# lab2_lyahovskij_buck.net
KiCad netlist of a schematic drawn in Altium Designer
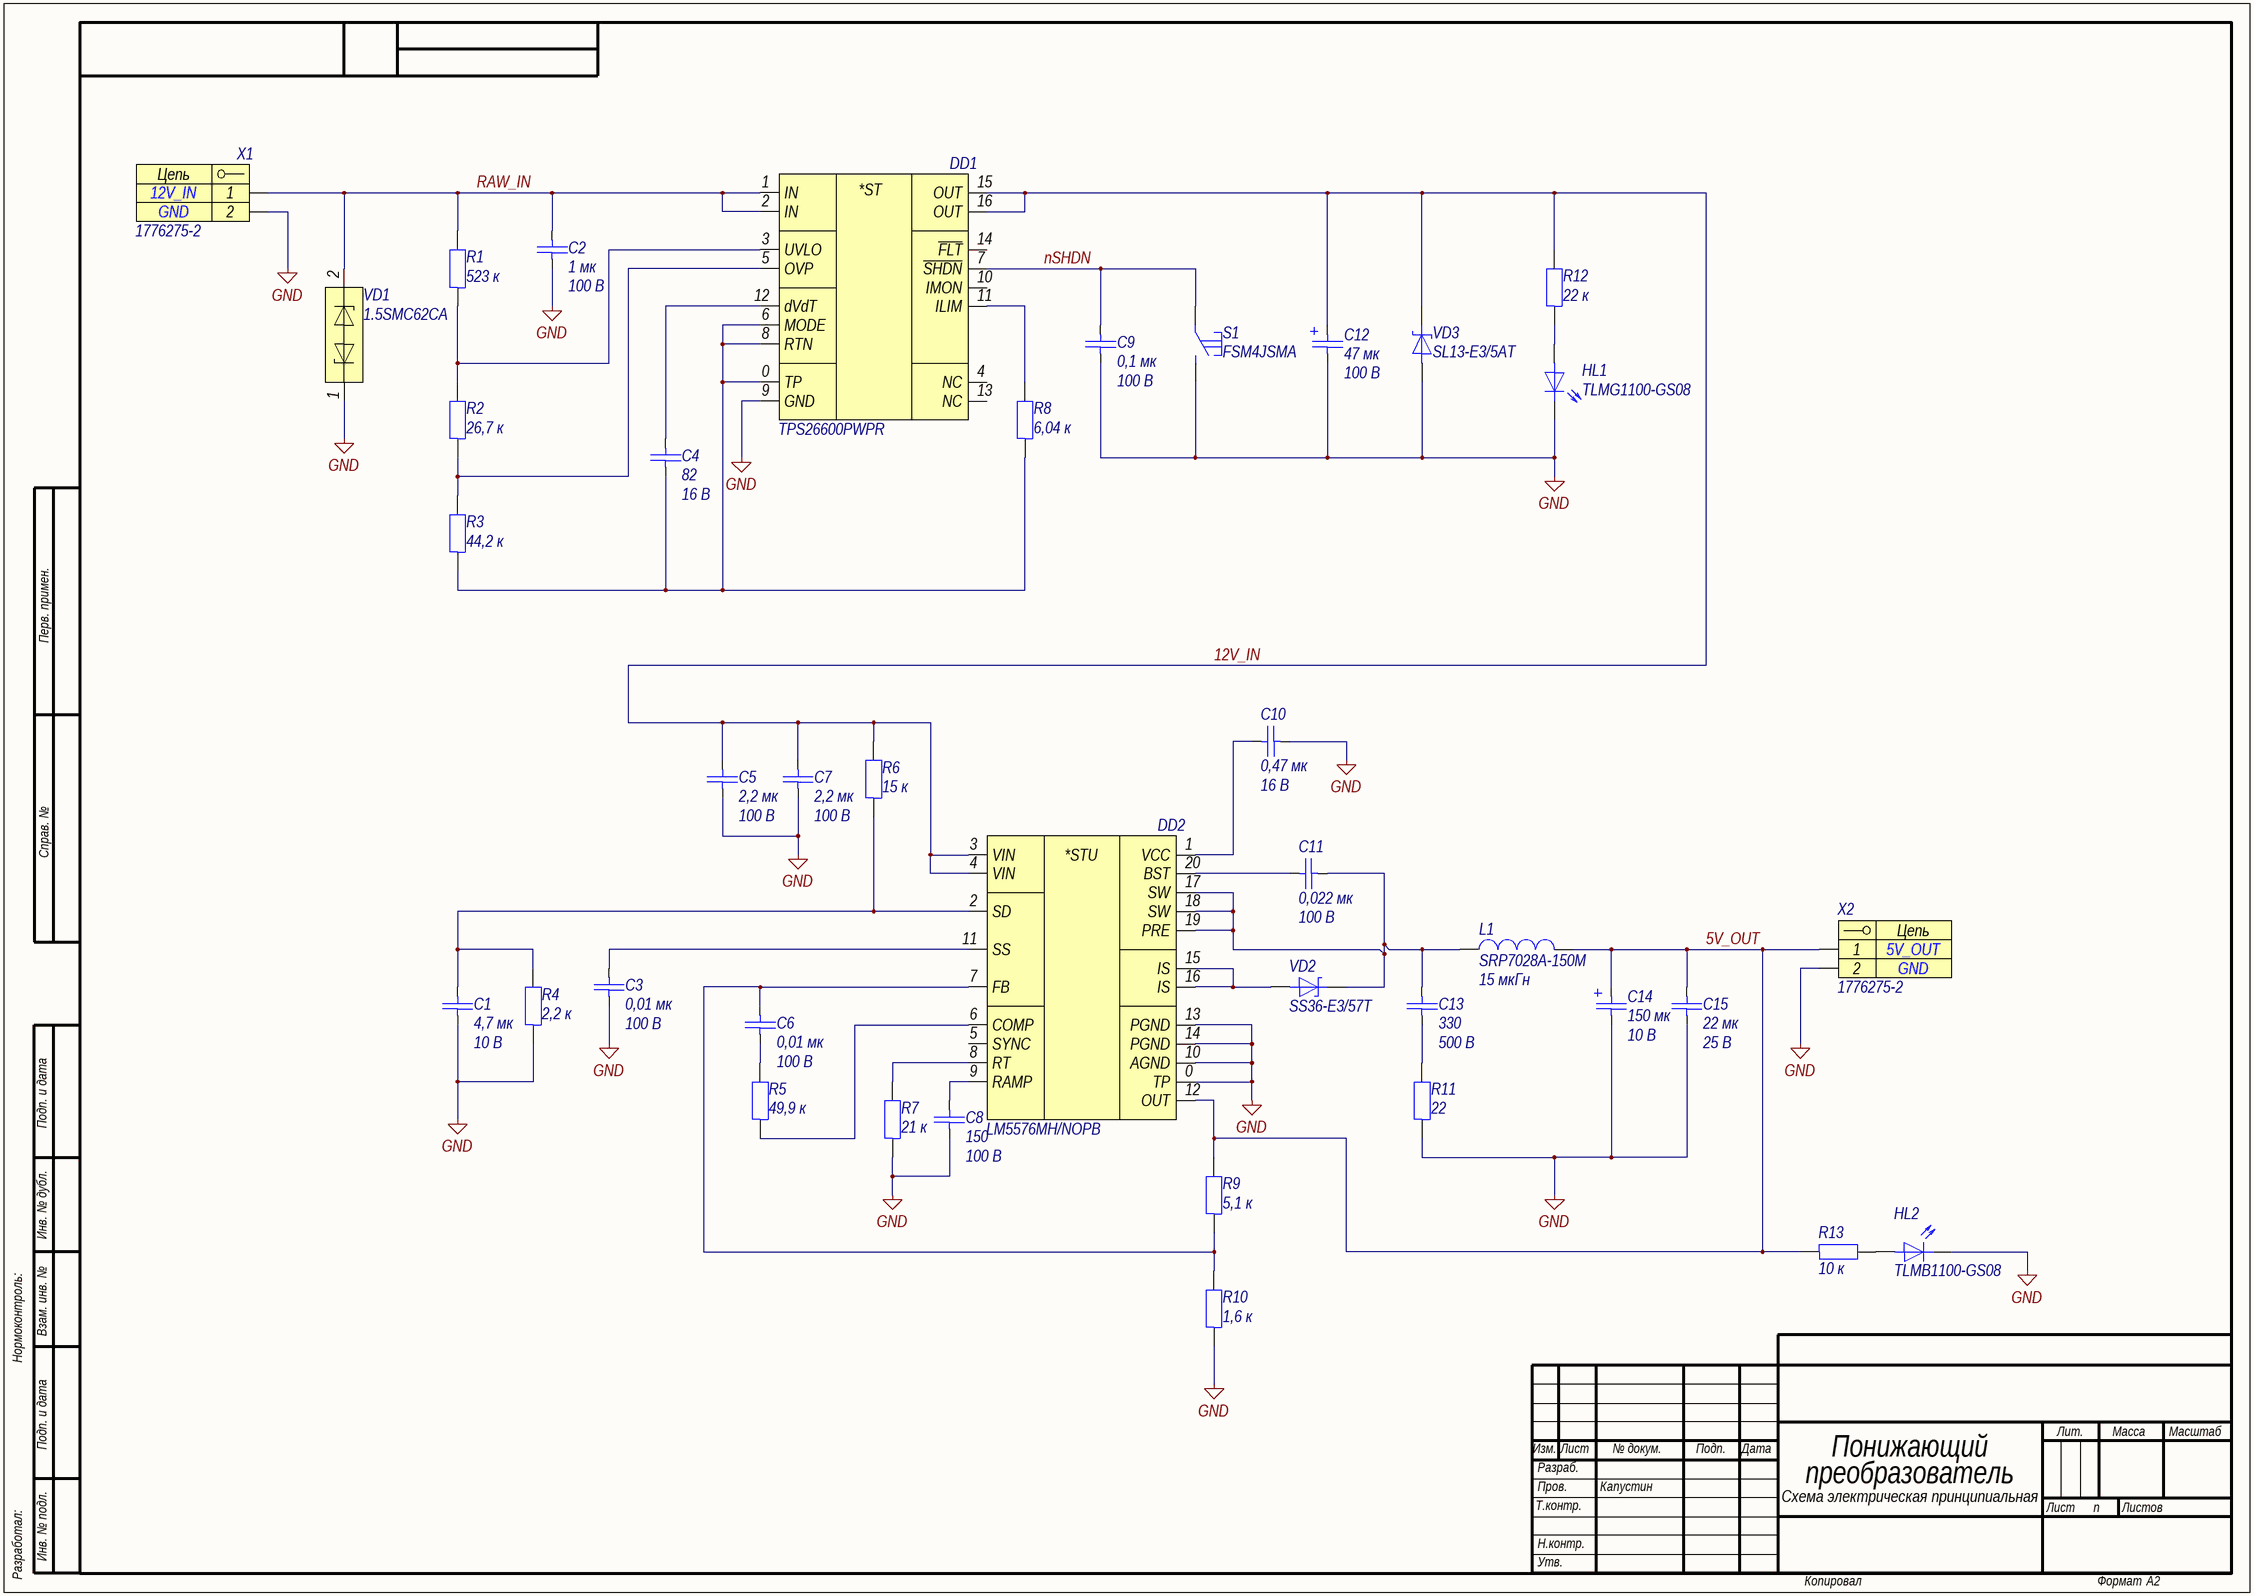
[diagram p0: lab2_lyahovskij_buck.SchDoc]

(export (version "E")
  (design (tool "Eeschema 10.0.6"))
  (components
    (comp (ref "C1")
      (value "4,7 мк")
      (footprint "C0603")
      (description "=Описание")
      (fields (field (name "НАПРЯЖЕНИЕ") "10 В"))
      (libsource (lib "Database_Students") (part "C-NONPOLAR"))
    )
    (comp (ref "C2")
      (value "1 мк")
      (footprint "C1206")
      (description "=Описание")
      (fields (field (name "НАПРЯЖЕНИЕ") "100 В"))
      (libsource (lib "Database_Students") (part "C-NONPOLAR"))
    )
    (comp (ref "C3")
      (value "0,01 мк")
      (footprint "C0603")
      (description "=Описание")
      (fields (field (name "НАПРЯЖЕНИЕ") "100 В"))
      (libsource (lib "Database_Students") (part "C-NONPOLAR"))
    )
    (comp (ref "C4")
      (value "82")
      (footprint "C0603")
      (description "=Описание")
      (fields (field (name "НАПРЯЖЕНИЕ") "16 В"))
      (libsource (lib "Database_Students") (part "C-NONPOLAR"))
    )
    (comp (ref "C5")
      (value "2,2 мк")
      (footprint "C1206")
      (description "=Описание")
      (fields (field (name "НАПРЯЖЕНИЕ") "100 В"))
      (libsource (lib "Database_Students") (part "C-NONPOLAR"))
    )
    (comp (ref "C6")
      (value "0,01 мк")
      (footprint "C0603")
      (description "=Описание")
      (fields (field (name "НАПРЯЖЕНИЕ") "100 В"))
      (libsource (lib "Database_Students") (part "C-NONPOLAR"))
    )
    (comp (ref "C7")
      (value "2,2 мк")
      (footprint "C1206")
      (description "=Описание")
      (fields (field (name "НАПРЯЖЕНИЕ") "100 В"))
      (libsource (lib "Database_Students") (part "C-NONPOLAR"))
    )
    (comp (ref "C8")
      (value "150")
      (footprint "C0805")
      (description "=Описание")
      (fields (field (name "НАПРЯЖЕНИЕ") "100 В"))
      (libsource (lib "Database_Students") (part "C-NONPOLAR"))
    )
    (comp (ref "C9")
      (value "0,1 мк")
      (footprint "C0603")
      (description "=Описание")
      (fields (field (name "НАПРЯЖЕНИЕ") "100 В"))
      (libsource (lib "Database_Students") (part "C-NONPOLAR"))
    )
    (comp (ref "C10")
      (value "0,47 мк")
      (footprint "C0603")
      (description "=Описание")
      (fields (field (name "НАПРЯЖЕНИЕ") "16 В"))
      (libsource (lib "Database_Students") (part "C-NONPOLAR"))
    )
    (comp (ref "C11")
      (value "0,022 мк")
      (footprint "C1210")
      (description "=Описание")
      (fields (field (name "НАПРЯЖЕНИЕ") "100 В"))
      (libsource (lib "Database_Students") (part "C-NONPOLAR"))
    )
    (comp (ref "C12")
      (value "47 мк")
      (footprint "CAPAE-1000X1000X1200")
      (description "=Описание")
      (fields (field (name "НАПРЯЖЕНИЕ") "100 В"))
      (libsource (lib "Database_Students") (part "C-POLAR"))
    )
    (comp (ref "C13")
      (value "330")
      (footprint "C1210")
      (description "=Описание")
      (fields (field (name "НАПРЯЖЕНИЕ") "500 В"))
      (libsource (lib "Database_Students") (part "C-NONPOLAR"))
    )
    (comp (ref "C14")
      (value "150 мк")
      (footprint "CAPAE-660X660X580")
      (description "=Описание")
      (fields (field (name "НАПРЯЖЕНИЕ") "10 В"))
      (libsource (lib "Database_Students") (part "C-POLAR"))
    )
    (comp (ref "C15")
      (value "22 мк")
      (footprint "C1210")
      (description "=Описание")
      (fields (field (name "НАПРЯЖЕНИЕ") "25 В"))
      (libsource (lib "Database_Students") (part "C-NONPOLAR"))
    )
    (comp (ref "DD1")
      (value "TPS26600PWPR")
      (footprint "HTSSOP-16")
      (description "=Описание")
      (libsource (lib "Database_Students") (part "TPS26600PWPR"))
    )
    (comp (ref "DD2")
      (value "LM5576MH/NOPB")
      (footprint "HTSSOP-20")
      (description "=Описание")
      (libsource (lib "Database_Students") (part "LM5576MH/NOPB"))
    )
    (comp (ref "HL1")
      (value "TLMG1100-GS08")
      (footprint "HL0603")
      (description "=Описание")
      (libsource (lib "Database_Students") (part "HL-COMMON"))
    )
    (comp (ref "HL2")
      (value "TLMB1100-GS08")
      (footprint "HL0603")
      (description "=Описание")
      (libsource (lib "Database_Students") (part "HL-COMMON"))
    )
    (comp (ref "L1")
      (value "SRP7028A-150M")
      (footprint "SRP-2-730X660X280")
      (description "=Описание")
      (fields (field (name "ИНДУКТИВНОСТЬ") "15 мкГн"))
      (libsource (lib "Database_Students") (part "INDUCTOR-COMMON"))
    )
    (comp (ref "R1")
      (value "523 к")
      (footprint "R0603")
      (description "=Описание")
      (libsource (lib "Database_Students") (part "R-COMMON"))
    )
    (comp (ref "R2")
      (value "26,7 к")
      (footprint "R0603")
      (description "=Описание")
      (libsource (lib "Database_Students") (part "R-COMMON"))
    )
    (comp (ref "R3")
      (value "44,2 к")
      (footprint "R0603")
      (description "=Описание")
      (libsource (lib "Database_Students") (part "R-COMMON"))
    )
    (comp (ref "R4")
      (value "2,2 к")
      (footprint "R0603")
      (description "=Описание")
      (libsource (lib "Database_Students") (part "R-COMMON"))
    )
    (comp (ref "R5")
      (value "49,9 к")
      (footprint "R0603")
      (description "=Описание")
      (libsource (lib "Database_Students") (part "R-COMMON"))
    )
    (comp (ref "R6")
      (value "15 к")
      (footprint "R0603")
      (description "=Описание")
      (libsource (lib "Database_Students") (part "R-COMMON"))
    )
    (comp (ref "R7")
      (value "21 к")
      (footprint "R0603")
      (description "=Описание")
      (libsource (lib "Database_Students") (part "R-COMMON"))
    )
    (comp (ref "R8")
      (value "6,04 к")
      (footprint "R0603")
      (description "=Описание")
      (libsource (lib "Database_Students") (part "R-COMMON"))
    )
    (comp (ref "R9")
      (value "5,1 к")
      (footprint "R0603")
      (description "=Описание")
      (libsource (lib "Database_Students") (part "R-COMMON"))
    )
    (comp (ref "R10")
      (value "1,6 к")
      (footprint "R0603")
      (description "=Описание")
      (libsource (lib "Database_Students") (part "R-COMMON"))
    )
    (comp (ref "R11")
      (value "22")
      (footprint "R0603")
      (description "=Описание")
      (libsource (lib "Database_Students") (part "R-COMMON"))
    )
    (comp (ref "R12")
      (value "22 к")
      (footprint "R0603")
      (description "=Описание")
      (libsource (lib "Database_Students") (part "R-COMMON"))
    )
    (comp (ref "R13")
      (value "10 к")
      (footprint "R0603")
      (description "=Описание")
      (libsource (lib "Database_Students") (part "R-COMMON"))
    )
    (comp (ref "S1")
      (value "FSM4JSMA")
      (footprint "FSM4JSMA")
      (description "=Описание")
      (libsource (lib "Database_Students") (part "BUTTON"))
    )
    (comp (ref "VD1")
      (value "1.5SMC62CA")
      (footprint "DO-214AB")
      (description "=Описание")
      (libsource (lib "Database_Students") (part "ZENER-BI-DIRECTIONAL"))
    )
    (comp (ref "VD2")
      (value "SS36-E3/57T")
      (footprint "DO-214AB")
      (description "=Описание")
      (libsource (lib "Database_Students") (part "DIODE-SCHOTTKY"))
    )
    (comp (ref "VD3")
      (value "SL13-E3/5AT")
      (footprint "DO-214AC")
      (description "=Описание")
      (libsource (lib "Database_Students") (part "DIODE-SCHOTTKY"))
    )
    (comp (ref "X1")
      (value "1776275-2")
      (footprint "1776275-2")
      (description "=Описание")
      (libsource (lib "Database_Students") (part "HEADER-2-TRM"))
    )
    (comp (ref "X2")
      (value "1776275-2")
      (footprint "1776275-2")
      (description "=Описание")
      (libsource (lib "") (part "HEADER-2-TRM_1"))
    )
  )
  (nets
    (net (code "1") (name "/5V_OUT") (class "Default")
      (node (ref "C14") (pin "1") (pinfunction "1_1") (pintype "passive"))
      (node (ref "C15") (pin "1") (pinfunction "1_1") (pintype "passive"))
      (node (ref "DD2") (pin "12") (pinfunction "OUT_12") (pintype "passive"))
      (node (ref "L1") (pin "2") (pinfunction "2_2") (pintype "passive"))
      (node (ref "R13") (pin "1") (pinfunction "1_1") (pintype "passive"))
      (node (ref "R9") (pin "2") (pinfunction "2_2") (pintype "passive"))
      (node (ref "X2") (pin "1") (pinfunction "1_1") (pintype "passive"))
    )
    (net (code "2") (name "/12V_IN") (class "Default")
      (node (ref "C12") (pin "1") (pinfunction "1_1") (pintype "passive"))
      (node (ref "C5") (pin "1") (pinfunction "1_1") (pintype "passive"))
      (node (ref "C7") (pin "1") (pinfunction "1_1") (pintype "passive"))
      (node (ref "DD1") (pin "15") (pinfunction "OUT_15") (pintype "passive"))
      (node (ref "DD1") (pin "16") (pinfunction "OUT_16") (pintype "passive"))
      (node (ref "DD2") (pin "3") (pinfunction "VIN_3") (pintype "passive"))
      (node (ref "DD2") (pin "4") (pinfunction "VIN_4") (pintype "passive"))
      (node (ref "R12") (pin "2") (pinfunction "2_2") (pintype "passive"))
      (node (ref "R6") (pin "2") (pinfunction "2_2") (pintype "passive"))
      (node (ref "VD3") (pin "1") (pinfunction "1_1") (pintype "passive"))
    )
    (net (code "3") (name "/RAW_IN") (class "Default")
      (node (ref "C2") (pin "1") (pinfunction "1_1") (pintype "passive"))
      (node (ref "DD1") (pin "1") (pinfunction "IN_1") (pintype "passive"))
      (node (ref "DD1") (pin "2") (pinfunction "IN_2") (pintype "passive"))
      (node (ref "R1") (pin "2") (pinfunction "2_2") (pintype "passive"))
      (node (ref "VD1") (pin "2") (pinfunction "2_2") (pintype "passive"))
      (node (ref "X1") (pin "1") (pinfunction "1_1") (pintype "passive"))
    )
    (net (code "4") (name "/nSHDN") (class "Default")
      (node (ref "C9") (pin "1") (pinfunction "1_1") (pintype "passive"))
      (node (ref "DD1") (pin "7") (pinfunction "~{SHDN}_7") (pintype "passive"))
      (node (ref "S1") (pin "1") (pinfunction "1_1") (pintype "passive"))
    )
    (net (code "5") (name "GND") (class "Default")
      (node (ref "C1") (pin "2") (pinfunction "2_2") (pintype "passive"))
      (node (ref "C10") (pin "2") (pinfunction "2_2") (pintype "passive"))
      (node (ref "C12") (pin "2") (pinfunction "2_2") (pintype "passive"))
      (node (ref "C14") (pin "2") (pinfunction "2_2") (pintype "passive"))
      (node (ref "C15") (pin "2") (pinfunction "2_2") (pintype "passive"))
      (node (ref "C2") (pin "2") (pinfunction "2_2") (pintype "passive"))
      (node (ref "C3") (pin "2") (pinfunction "2_2") (pintype "passive"))
      (node (ref "C5") (pin "2") (pinfunction "2_2") (pintype "passive"))
      (node (ref "C7") (pin "2") (pinfunction "2_2") (pintype "passive"))
      (node (ref "C8") (pin "2") (pinfunction "2_2") (pintype "passive"))
      (node (ref "C9") (pin "2") (pinfunction "2_2") (pintype "passive"))
      (node (ref "DD1") (pin "9") (pinfunction "GND_9") (pintype "passive"))
      (node (ref "DD2") (pin "0") (pinfunction "TP_0") (pintype "passive"))
      (node (ref "DD2") (pin "10") (pinfunction "AGND_10") (pintype "passive"))
      (node (ref "DD2") (pin "13") (pinfunction "PGND_13") (pintype "passive"))
      (node (ref "DD2") (pin "14") (pinfunction "PGND_14") (pintype "passive"))
      (node (ref "HL1") (pin "1") (pinfunction "1_1") (pintype "passive"))
      (node (ref "HL2") (pin "1") (pinfunction "1_1") (pintype "passive"))
      (node (ref "R10") (pin "1") (pinfunction "1_1") (pintype "passive"))
      (node (ref "R11") (pin "1") (pinfunction "1_1") (pintype "passive"))
      (node (ref "R4") (pin "1") (pinfunction "1_1") (pintype "passive"))
      (node (ref "R7") (pin "1") (pinfunction "1_1") (pintype "passive"))
      (node (ref "S1") (pin "2") (pinfunction "2_2") (pintype "passive"))
      (node (ref "VD1") (pin "1") (pinfunction "1_1") (pintype "passive"))
      (node (ref "VD3") (pin "2") (pinfunction "2_2") (pintype "passive"))
      (node (ref "X1") (pin "2") (pinfunction "2_2") (pintype "passive"))
      (node (ref "X2") (pin "2") (pinfunction "2_2") (pintype "passive"))
    )
    (net (code "6") (name "Net-(C6-Pad2)") (class "Default")
      (node (ref "C6") (pin "2") (pinfunction "2_2") (pintype "passive"))
      (node (ref "R5") (pin "2") (pinfunction "2_2") (pintype "passive"))
    )
    (net (code "7") (name "Net-(C13-Pad2)") (class "Default")
      (node (ref "C13") (pin "2") (pinfunction "2_2") (pintype "passive"))
      (node (ref "R11") (pin "2") (pinfunction "2_2") (pintype "passive"))
    )
    (net (code "8") (name "Net-(DD1-ILIM)") (class "Default")
      (node (ref "DD1") (pin "11") (pinfunction "ILIM_11") (pintype "passive"))
      (node (ref "R8") (pin "2") (pinfunction "2_2") (pintype "passive"))
    )
    (net (code "9") (name "Net-(DD1-MODE)") (class "Default")
      (node (ref "C4") (pin "2") (pinfunction "2_2") (pintype "passive"))
      (node (ref "DD1") (pin "0") (pinfunction "TP_0") (pintype "passive"))
      (node (ref "DD1") (pin "6") (pinfunction "MODE_6") (pintype "passive"))
      (node (ref "DD1") (pin "8") (pinfunction "RTN_8") (pintype "passive"))
      (node (ref "R3") (pin "1") (pinfunction "1_1") (pintype "passive"))
      (node (ref "R8") (pin "1") (pinfunction "1_1") (pintype "passive"))
    )
    (net (code "10") (name "Net-(DD1-OVP)") (class "Default")
      (node (ref "DD1") (pin "5") (pinfunction "OVP_5") (pintype "passive"))
      (node (ref "R2") (pin "1") (pinfunction "1_1") (pintype "passive"))
      (node (ref "R3") (pin "2") (pinfunction "2_2") (pintype "passive"))
    )
    (net (code "11") (name "Net-(DD1-UVLO)") (class "Default")
      (node (ref "DD1") (pin "3") (pinfunction "UVLO_3") (pintype "passive"))
      (node (ref "R1") (pin "1") (pinfunction "1_1") (pintype "passive"))
      (node (ref "R2") (pin "2") (pinfunction "2_2") (pintype "passive"))
    )
    (net (code "12") (name "Net-(DD1-dVdT)") (class "Default")
      (node (ref "C4") (pin "1") (pinfunction "1_1") (pintype "passive"))
      (node (ref "DD1") (pin "12") (pinfunction "dVdT_12") (pintype "passive"))
    )
    (net (code "13") (name "Net-(DD2-BST)") (class "Default")
      (node (ref "C11") (pin "1") (pinfunction "1_1") (pintype "passive"))
      (node (ref "DD2") (pin "20") (pinfunction "BST_20") (pintype "passive"))
    )
    (net (code "14") (name "Net-(DD2-COMP)") (class "Default")
      (node (ref "DD2") (pin "6") (pinfunction "COMP_6") (pintype "passive"))
      (node (ref "R5") (pin "1") (pinfunction "1_1") (pintype "passive"))
    )
    (net (code "15") (name "Net-(DD2-FB)") (class "Default")
      (node (ref "C6") (pin "1") (pinfunction "1_1") (pintype "passive"))
      (node (ref "DD2") (pin "7") (pinfunction "FB_7") (pintype "passive"))
      (node (ref "R10") (pin "2") (pinfunction "2_2") (pintype "passive"))
      (node (ref "R9") (pin "1") (pinfunction "1_1") (pintype "passive"))
    )
    (net (code "16") (name "Net-(DD2-IS-Pad15)") (class "Default")
      (node (ref "DD2") (pin "15") (pinfunction "IS_15") (pintype "passive"))
      (node (ref "DD2") (pin "16") (pinfunction "IS_16") (pintype "passive"))
      (node (ref "VD2") (pin "2") (pinfunction "2_2") (pintype "passive"))
    )
    (net (code "17") (name "Net-(DD2-PRE)") (class "Default")
      (node (ref "C11") (pin "2") (pinfunction "2_2") (pintype "passive"))
      (node (ref "C13") (pin "1") (pinfunction "1_1") (pintype "passive"))
      (node (ref "DD2") (pin "17") (pinfunction "SW_17") (pintype "passive"))
      (node (ref "DD2") (pin "18") (pinfunction "SW_18") (pintype "passive"))
      (node (ref "DD2") (pin "19") (pinfunction "PRE_19") (pintype "passive"))
      (node (ref "L1") (pin "1") (pinfunction "1_1") (pintype "passive"))
      (node (ref "VD2") (pin "1") (pinfunction "1_1") (pintype "passive"))
    )
    (net (code "18") (name "Net-(DD2-RAMP)") (class "Default")
      (node (ref "C8") (pin "1") (pinfunction "1_1") (pintype "passive"))
      (node (ref "DD2") (pin "9") (pinfunction "RAMP_9") (pintype "passive"))
    )
    (net (code "19") (name "Net-(DD2-RT)") (class "Default")
      (node (ref "DD2") (pin "8") (pinfunction "RT_8") (pintype "passive"))
      (node (ref "R7") (pin "2") (pinfunction "2_2") (pintype "passive"))
    )
    (net (code "20") (name "Net-(DD2-SD)") (class "Default")
      (node (ref "C1") (pin "1") (pinfunction "1_1") (pintype "passive"))
      (node (ref "DD2") (pin "2") (pinfunction "SD_2") (pintype "passive"))
      (node (ref "R4") (pin "2") (pinfunction "2_2") (pintype "passive"))
      (node (ref "R6") (pin "1") (pinfunction "1_1") (pintype "passive"))
    )
    (net (code "21") (name "Net-(DD2-SS)") (class "Default")
      (node (ref "C3") (pin "1") (pinfunction "1_1") (pintype "passive"))
      (node (ref "DD2") (pin "11") (pinfunction "SS_11") (pintype "passive"))
    )
    (net (code "22") (name "Net-(DD2-VCC)") (class "Default")
      (node (ref "C10") (pin "1") (pinfunction "1_1") (pintype "passive"))
      (node (ref "DD2") (pin "1") (pinfunction "VCC_1") (pintype "passive"))
    )
    (net (code "23") (name "Net-(HL1-Pad2)") (class "Default")
      (node (ref "HL1") (pin "2") (pinfunction "2_2") (pintype "passive"))
      (node (ref "R12") (pin "1") (pinfunction "1_1") (pintype "passive"))
    )
    (net (code "24") (name "Net-(HL2-Pad2)") (class "Default")
      (node (ref "HL2") (pin "2") (pinfunction "2_2") (pintype "passive"))
      (node (ref "R13") (pin "2") (pinfunction "2_2") (pintype "passive"))
    )
    (net (code "25") (name "unconnected-(DD1-IMON-Pad10)") (class "Default")
      (node (ref "DD1") (pin "10") (pinfunction "IMON_10") (pintype "passive"))
    )
    (net (code "26") (name "unconnected-(DD1-NC-Pad4)") (class "Default")
      (node (ref "DD1") (pin "4") (pinfunction "NC_4") (pintype "passive"))
    )
    (net (code "27") (name "unconnected-(DD1-NC-Pad13)") (class "Default")
      (node (ref "DD1") (pin "13") (pinfunction "NC_13") (pintype "passive"))
    )
    (net (code "28") (name "unconnected-(DD1-~{FLT}-Pad14)") (class "Default")
      (node (ref "DD1") (pin "14") (pinfunction "~{FLT}_14") (pintype "passive"))
    )
    (net (code "29") (name "unconnected-(DD2-SYNC-Pad5)") (class "Default")
      (node (ref "DD2") (pin "5") (pinfunction "SYNC_5") (pintype "passive"))
    )
  )
)
